# sensor_board.net
KiCad netlist of a schematic drawn in Altium Designer
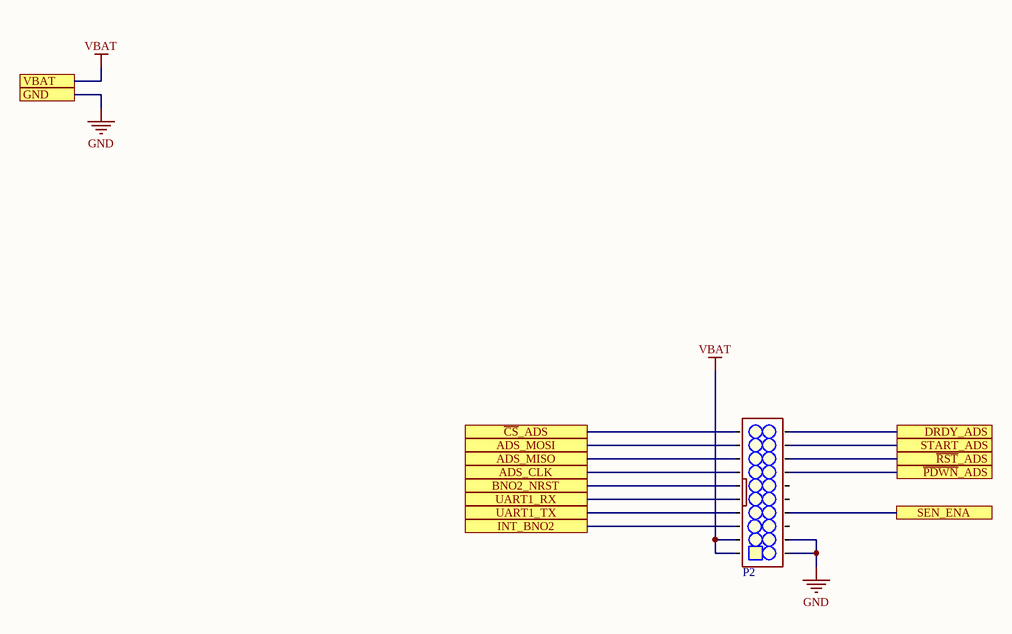
[diagram p0: sensor_board.SchDoc]

(export (version "E")
  (design (tool "Eeschema 10.0.6"))
  (components
    (comp (ref "P2")
      (value "2x10 Ribbon Header")
      (footprint "2x10_RIBBON_CABLE_CON")
      (description "2.54 mm")
      (fields (field (name "MANUFACTURER PART NO") "302-S201"))
      (libsource (lib "jclib") (part "2x10 Ribbon Header"))
    )
  )
  (nets
    (net (code "1") (name "/ADS_CLK") (class "Default")
      (node (ref "P2") (pin "7") (pinfunction "7_7") (pintype "passive"))
    )
    (net (code "2") (name "/ADS_MISO") (class "Default")
      (node (ref "P2") (pin "8") (pinfunction "8_8") (pintype "passive"))
    )
    (net (code "3") (name "/ADS_MOSI") (class "Default")
      (node (ref "P2") (pin "9") (pinfunction "9_9") (pintype "passive"))
    )
    (net (code "4") (name "/BNO2_NRST") (class "Default")
      (node (ref "P2") (pin "6") (pinfunction "6_6") (pintype "passive"))
    )
    (net (code "5") (name "/DRDY_ADS") (class "Default")
      (node (ref "P2") (pin "11") (pinfunction "11_11") (pintype "passive"))
    )
    (net (code "6") (name "/INT_BNO2") (class "Default")
      (node (ref "P2") (pin "3") (pinfunction "3_3") (pintype "passive"))
    )
    (net (code "7") (name "/SEN_ENA") (class "Default")
      (node (ref "P2") (pin "17") (pinfunction "17_17") (pintype "passive"))
    )
    (net (code "8") (name "/START_ADS") (class "Default")
      (node (ref "P2") (pin "12") (pinfunction "12_12") (pintype "passive"))
    )
    (net (code "9") (name "/UART1_RX") (class "Default")
      (node (ref "P2") (pin "5") (pinfunction "5_5") (pintype "passive"))
    )
    (net (code "10") (name "/UART1_TX") (class "Default")
      (node (ref "P2") (pin "4") (pinfunction "4_4") (pintype "passive"))
    )
    (net (code "11") (name "/~{CS}_ADS") (class "Default")
      (node (ref "P2") (pin "10") (pinfunction "10_10") (pintype "passive"))
    )
    (net (code "12") (name "/~{PDWN}_ADS") (class "Default")
      (node (ref "P2") (pin "14") (pinfunction "14_14") (pintype "passive"))
    )
    (net (code "13") (name "/~{RST}_ADS") (class "Default")
      (node (ref "P2") (pin "13") (pinfunction "13_13") (pintype "passive"))
    )
    (net (code "14") (name "GND") (class "Default")
      (node (ref "P2") (pin "19") (pinfunction "19_19") (pintype "passive"))
      (node (ref "P2") (pin "20") (pinfunction "20_20") (pintype "passive"))
    )
    (net (code "15") (name "VBAT") (class "Default")
      (node (ref "P2") (pin "1") (pinfunction "1_1") (pintype "passive"))
      (node (ref "P2") (pin "2") (pinfunction "2_2") (pintype "passive"))
    )
    (net (code "16") (name "unconnected-(P2-Pad15)") (class "Default")
      (node (ref "P2") (pin "15") (pinfunction "15_15") (pintype "passive"))
    )
    (net (code "17") (name "unconnected-(P2-Pad16)") (class "Default")
      (node (ref "P2") (pin "16") (pinfunction "16_16") (pintype "passive"))
    )
    (net (code "18") (name "unconnected-(P2-Pad18)") (class "Default")
      (node (ref "P2") (pin "18") (pinfunction "18_18") (pintype "passive"))
    )
  )
)
